# left_thumb.net
KiCad netlist of a schematic drawn in EAGLE
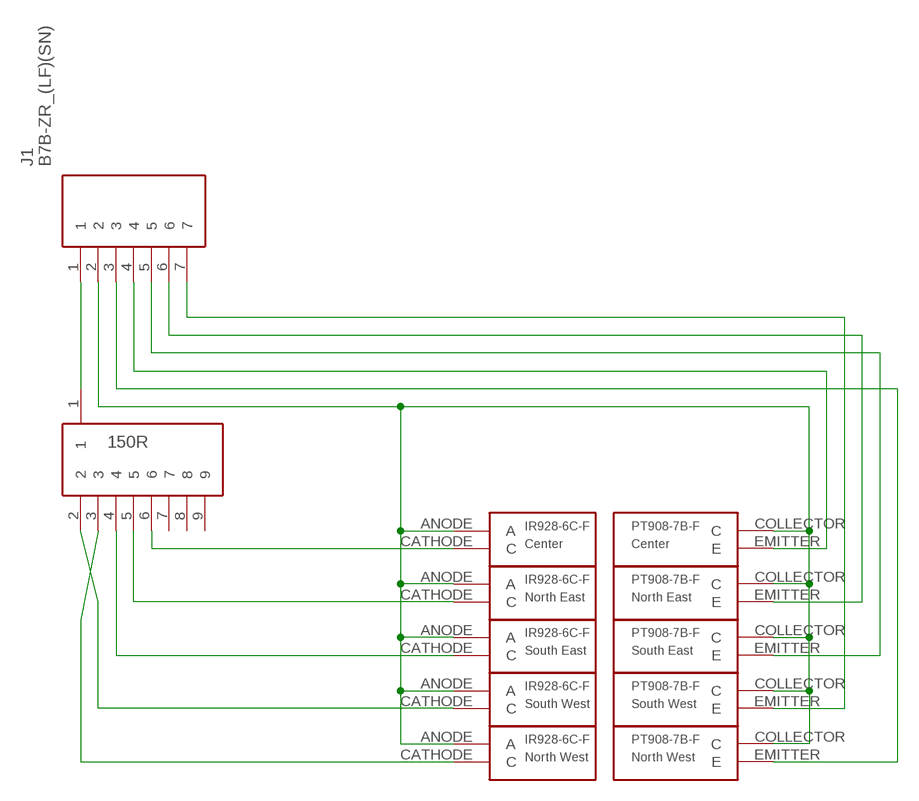
[diagram p0: schematic, sheet 1]

(export (version "E")
  (design (tool "Eeschema 10.0.6"))
  (components
    (comp (ref "J1")
      (value "B7B-ZR_(LF)(SN)")
      (footprint "eagle-import:SHDR7W50P0X150_1X7_1200X350X45")
      (fields
        (field (name "MANUFACTURER_PART_NUMBER") "B7B-ZR (LF)(SN)")
        (field (name "RS_PART_NUMBER") "7620828")
      )
      (libsource (lib "eagle-import") (part "B7B-ZR_(LF)(SN)"))
    )
    (comp (ref "LED1")
      (value "Center")
      (footprint "eagle-import:IR928-6C-F")
      (libsource (lib "eagle-import") (part "IR928-6C-F"))
    )
    (comp (ref "LED2")
      (value "North East")
      (footprint "eagle-import:IR928-6C-F")
      (libsource (lib "eagle-import") (part "IR928-6C-F"))
    )
    (comp (ref "LED3")
      (value "South East")
      (footprint "eagle-import:IR928-6C-F")
      (libsource (lib "eagle-import") (part "IR928-6C-F"))
    )
    (comp (ref "LED4")
      (value "South West")
      (footprint "eagle-import:IR928-6C-F")
      (libsource (lib "eagle-import") (part "IR928-6C-F"))
    )
    (comp (ref "LED5")
      (value "North West")
      (footprint "eagle-import:IR928-6C-F")
      (libsource (lib "eagle-import") (part "IR928-6C-F"))
    )
    (comp (ref "PT1")
      (value "Center")
      (footprint "eagle-import:PT908-7B-F")
      (libsource (lib "eagle-import") (part "PT908-7B-F"))
    )
    (comp (ref "PT2")
      (value "North East")
      (footprint "eagle-import:PT908-7B-F")
      (libsource (lib "eagle-import") (part "PT908-7B-F"))
    )
    (comp (ref "PT3")
      (value "South East")
      (footprint "eagle-import:PT908-7B-F")
      (libsource (lib "eagle-import") (part "PT908-7B-F"))
    )
    (comp (ref "PT4")
      (value "South West")
      (footprint "eagle-import:PT908-7B-F")
      (libsource (lib "eagle-import") (part "PT908-7B-F"))
    )
    (comp (ref "PT5")
      (value "North West")
      (footprint "eagle-import:PT908-7B-F")
      (libsource (lib "eagle-import") (part "PT908-7B-F"))
    )
    (comp (ref "RN1")
      (value "150R")
      (footprint "eagle-import:9PIN-RESISTOR-NETWORK")
      (libsource (lib "eagle-import") (part "9PIN-RESISTOR-NETWORK9PIN-RESISTOR-NETWORK"))
    )
  )
  (nets
    (net (code "1") (name "Net-(J1-Pad1)") (class "Default")
      (node (ref "J1") (pin "1") (pinfunction "1_1") (pintype "bidirectional"))
      (node (ref "RN1") (pin "1") (pinfunction "1_1") (pintype "bidirectional"))
    )
    (net (code "2") (name "Net-(LED1-A)") (class "Default")
      (node (ref "J1") (pin "2") (pinfunction "2_2") (pintype "bidirectional"))
      (node (ref "LED1") (pin "ANODE") (pinfunction "A_ANODE") (pintype "input"))
      (node (ref "LED2") (pin "ANODE") (pinfunction "A_ANODE") (pintype "input"))
      (node (ref "LED3") (pin "ANODE") (pinfunction "A_ANODE") (pintype "input"))
      (node (ref "LED4") (pin "ANODE") (pinfunction "A_ANODE") (pintype "input"))
      (node (ref "LED5") (pin "ANODE") (pinfunction "A_ANODE") (pintype "input"))
      (node (ref "PT1") (pin "COLLECTOR") (pinfunction "C_COLLECTOR") (pintype "input"))
      (node (ref "PT2") (pin "COLLECTOR") (pinfunction "C_COLLECTOR") (pintype "input"))
      (node (ref "PT3") (pin "COLLECTOR") (pinfunction "C_COLLECTOR") (pintype "input"))
      (node (ref "PT4") (pin "COLLECTOR") (pinfunction "C_COLLECTOR") (pintype "input"))
      (node (ref "PT5") (pin "COLLECTOR") (pinfunction "C_COLLECTOR") (pintype "input"))
    )
    (net (code "3") (name "Net-(LED1-C)") (class "Default")
      (node (ref "LED1") (pin "CATHODE") (pinfunction "C_CATHODE") (pintype "output"))
      (node (ref "RN1") (pin "6") (pinfunction "6_6") (pintype "bidirectional"))
    )
    (net (code "4") (name "Net-(LED2-C)") (class "Default")
      (node (ref "LED2") (pin "CATHODE") (pinfunction "C_CATHODE") (pintype "output"))
      (node (ref "RN1") (pin "5") (pinfunction "5_5") (pintype "bidirectional"))
    )
    (net (code "5") (name "Net-(LED3-C)") (class "Default")
      (node (ref "LED3") (pin "CATHODE") (pinfunction "C_CATHODE") (pintype "output"))
      (node (ref "RN1") (pin "4") (pinfunction "4_4") (pintype "bidirectional"))
    )
    (net (code "6") (name "Net-(LED4-C)") (class "Default")
      (node (ref "LED4") (pin "CATHODE") (pinfunction "C_CATHODE") (pintype "output"))
      (node (ref "RN1") (pin "2") (pinfunction "2_2") (pintype "bidirectional"))
    )
    (net (code "7") (name "Net-(LED5-C)") (class "Default")
      (node (ref "LED5") (pin "CATHODE") (pinfunction "C_CATHODE") (pintype "output"))
      (node (ref "RN1") (pin "3") (pinfunction "3_3") (pintype "bidirectional"))
    )
    (net (code "8") (name "Net-(PT1-E)") (class "Default")
      (node (ref "J1") (pin "4") (pinfunction "4_4") (pintype "bidirectional"))
      (node (ref "PT1") (pin "EMITTER") (pinfunction "E_EMITTER") (pintype "output"))
    )
    (net (code "9") (name "Net-(PT2-E)") (class "Default")
      (node (ref "J1") (pin "6") (pinfunction "6_6") (pintype "bidirectional"))
      (node (ref "PT2") (pin "EMITTER") (pinfunction "E_EMITTER") (pintype "output"))
    )
    (net (code "10") (name "Net-(PT3-E)") (class "Default")
      (node (ref "J1") (pin "5") (pinfunction "5_5") (pintype "bidirectional"))
      (node (ref "PT3") (pin "EMITTER") (pinfunction "E_EMITTER") (pintype "output"))
    )
    (net (code "11") (name "Net-(PT4-E)") (class "Default")
      (node (ref "J1") (pin "7") (pinfunction "7_7") (pintype "bidirectional"))
      (node (ref "PT4") (pin "EMITTER") (pinfunction "E_EMITTER") (pintype "output"))
    )
    (net (code "12") (name "Net-(PT5-E)") (class "Default")
      (node (ref "J1") (pin "3") (pinfunction "3_3") (pintype "bidirectional"))
      (node (ref "PT5") (pin "EMITTER") (pinfunction "E_EMITTER") (pintype "output"))
    )
    (net (code "13") (name "unconnected-(RN1-Pad7)") (class "Default")
      (node (ref "RN1") (pin "7") (pinfunction "7_7") (pintype "bidirectional"))
    )
    (net (code "14") (name "unconnected-(RN1-Pad8)") (class "Default")
      (node (ref "RN1") (pin "8") (pinfunction "8_8") (pintype "bidirectional"))
    )
    (net (code "15") (name "unconnected-(RN1-Pad9)") (class "Default")
      (node (ref "RN1") (pin "9") (pinfunction "9_9") (pintype "bidirectional"))
    )
  )
)
